# SparkFun_Noisy_Cricket.net
KiCad netlist of a schematic drawn in EAGLE
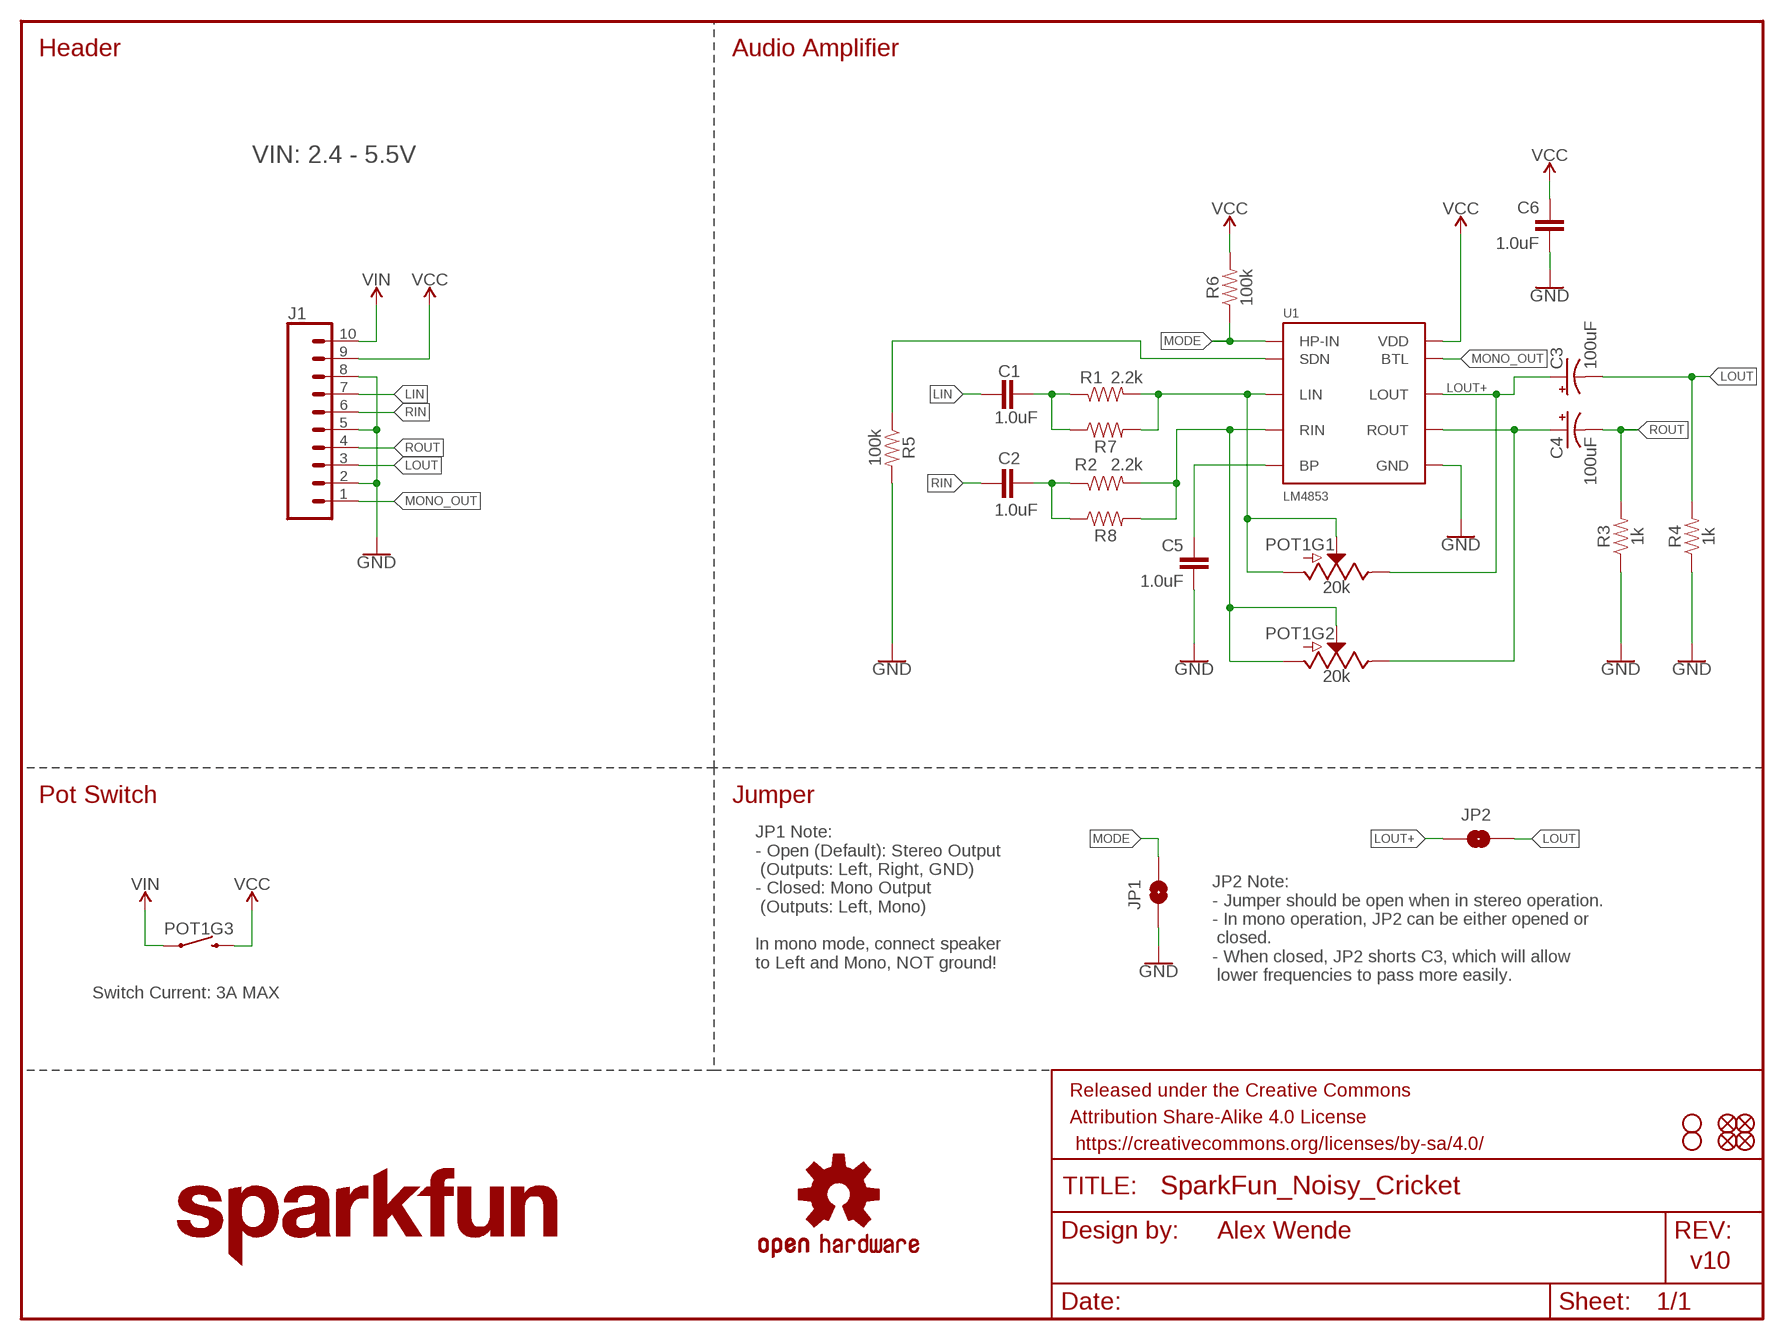
[diagram p0: schematic, sheet 1]

(export (version "E")
  (design (tool "Eeschema 10.0.6"))
  (components
    (comp (ref "C1")
      (value "1.0uF")
      (footprint "eagle-import:0603")
      (libsource (lib "eagle-import") (part "1.0UF-0603-16V-10%-X7R"))
    )
    (comp (ref "C2")
      (value "1.0uF")
      (footprint "eagle-import:0603")
      (libsource (lib "eagle-import") (part "1.0UF-0603-16V-10%-X7R"))
    )
    (comp (ref "C3")
      (value "100uF")
      (footprint "eagle-import:PANASONIC_D")
      (libsource (lib "eagle-import") (part "100UF-POLAR-25V-20%(ELEC)"))
    )
    (comp (ref "C4")
      (value "100uF")
      (footprint "eagle-import:PANASONIC_D")
      (libsource (lib "eagle-import") (part "100UF-POLAR-25V-20%(ELEC)"))
    )
    (comp (ref "C5")
      (value "1.0uF")
      (footprint "eagle-import:0603")
      (libsource (lib "eagle-import") (part "1.0UF-0603-16V-10%-X7R"))
    )
    (comp (ref "C6")
      (value "1.0uF")
      (footprint "eagle-import:0603")
      (libsource (lib "eagle-import") (part "1.0UF-0603-16V-10%-X7R"))
    )
    (comp (ref "FD1")
      (value "FIDUCIALUFIDUCIAL")
      (footprint "eagle-import:FIDUCIAL-MICRO")
      (libsource (lib "eagle-import") (part "FIDUCIALUFIDUCIAL"))
    )
    (comp (ref "FD2")
      (value "FIDUCIALUFIDUCIAL")
      (footprint "eagle-import:FIDUCIAL-MICRO")
      (libsource (lib "eagle-import") (part "FIDUCIALUFIDUCIAL"))
    )
    (comp (ref "FD3")
      (value "FIDUCIALUFIDUCIAL")
      (footprint "eagle-import:FIDUCIAL-MICRO")
      (libsource (lib "eagle-import") (part "FIDUCIALUFIDUCIAL"))
    )
    (comp (ref "FD4")
      (value "FIDUCIALUFIDUCIAL")
      (footprint "eagle-import:FIDUCIAL-MICRO")
      (libsource (lib "eagle-import") (part "FIDUCIALUFIDUCIAL"))
    )
    (comp (ref "FRAME1")
      (value "FRAME-LETTER")
      (footprint "eagle-import:CREATIVE_COMMONS")
      (libsource (lib "eagle-import") (part "FRAME-LETTER"))
    )
    (comp (ref "H1")
      (value "STAND-OFF")
      (footprint "eagle-import:STAND-OFF")
      (libsource (lib "eagle-import") (part "STAND-OFF"))
    )
    (comp (ref "H2")
      (value "STAND-OFF")
      (footprint "eagle-import:STAND-OFF")
      (libsource (lib "eagle-import") (part "STAND-OFF"))
    )
    (comp (ref "J1")
      (value "CONN_10NO_SILK_PTH_FEMALE")
      (footprint "eagle-import:1X10_NO_SILK")
      (libsource (lib "eagle-import") (part "CONN_10NO_SILK_PTH_FEMALE"))
    )
    (comp (ref "JP1")
      (value "JUMPER-SMT_2_NO_NO-SILK")
      (footprint "eagle-import:SMT-JUMPER_2_NO_NO-SILK")
      (libsource (lib "eagle-import") (part "JUMPER-SMT_2_NO_NO-SILK"))
    )
    (comp (ref "JP2")
      (value "JUMPER-SMT_2_NO_NO-SILK")
      (footprint "eagle-import:SMT-JUMPER_2_NO_NO-SILK")
      (libsource (lib "eagle-import") (part "JUMPER-SMT_2_NO_NO-SILK"))
    )
    (comp (ref "LOGO1")
      (value "SFE_LOGO_NAME.1_INCH")
      (footprint "eagle-import:SFE_LOGO_NAME_.1")
      (libsource (lib "eagle-import") (part "SFE_LOGO_NAME.1_INCH"))
    )
    (comp (ref "LOGO2")
      (value "OSHW-LOGOS")
      (footprint "eagle-import:OSHW-LOGO-S")
      (libsource (lib "eagle-import") (part "OSHW-LOGOS"))
    )
    (comp (ref "POT1")
      (value "20k")
      (footprint "eagle-import:POT-DUAL-SWITCH-PTH")
      (libsource (lib "eagle-import") (part "POTENTIOMETER_DUAL_W/SWITCH"))
    )
    (comp (ref "R1")
      (value "2.2k")
      (footprint "eagle-import:0603")
      (libsource (lib "eagle-import") (part "2.2KOHM-0603-1/10W-1%"))
    )
    (comp (ref "R2")
      (value "2.2k")
      (footprint "eagle-import:0603")
      (libsource (lib "eagle-import") (part "2.2KOHM-0603-1/10W-1%"))
    )
    (comp (ref "R3")
      (value "1k")
      (footprint "eagle-import:0603")
      (libsource (lib "eagle-import") (part "1KOHM-0603-1/10W-1%"))
    )
    (comp (ref "R4")
      (value "1k")
      (footprint "eagle-import:0603")
      (libsource (lib "eagle-import") (part "1KOHM-0603-1/10W-1%"))
    )
    (comp (ref "R5")
      (value "100k")
      (footprint "eagle-import:0603")
      (libsource (lib "eagle-import") (part "100KOHM-0603-1/10W-1%"))
    )
    (comp (ref "R6")
      (value "100k")
      (footprint "eagle-import:0603")
      (libsource (lib "eagle-import") (part "100KOHM-0603-1/10W-1%"))
    )
    (comp (ref "R7")
      (value "RESISTORAXIAL-0.3-KIT")
      (footprint "eagle-import:AXIAL-0.3-KIT")
      (libsource (lib "eagle-import") (part "RESISTORAXIAL-0.3-KIT"))
    )
    (comp (ref "R8")
      (value "RESISTORAXIAL-0.3-KIT")
      (footprint "eagle-import:AXIAL-0.3-KIT")
      (libsource (lib "eagle-import") (part "RESISTORAXIAL-0.3-KIT"))
    )
    (comp (ref "U1")
      (value "LM4853")
      (footprint "eagle-import:TFSOP-10")
      (libsource (lib "eagle-import") (part "LM4853"))
    )
  )
  (nets
    (net (code "1") (name "GND") (class "Default")
      (node (ref "C5") (pin "2") (pinfunction "2_2") (pintype "passive"))
      (node (ref "C6") (pin "2") (pinfunction "2_2") (pintype "passive"))
      (node (ref "J1") (pin "2") (pinfunction "2_2") (pintype "passive"))
      (node (ref "J1") (pin "5") (pinfunction "5_5") (pintype "passive"))
      (node (ref "J1") (pin "8") (pinfunction "8_8") (pintype "passive"))
      (node (ref "JP1") (pin "1") (pinfunction "1_1") (pintype "passive"))
      (node (ref "R3") (pin "1") (pinfunction "1_1") (pintype "passive"))
      (node (ref "R4") (pin "1") (pinfunction "1_1") (pintype "passive"))
      (node (ref "R5") (pin "2") (pinfunction "2_2") (pintype "passive"))
      (node (ref "U1") (pin "GND") (pinfunction "GND_GND") (pintype "bidirectional"))
    )
    (net (code "2") (name "LIN") (class "Default")
      (node (ref "C1") (pin "1") (pinfunction "1_1") (pintype "passive"))
      (node (ref "J1") (pin "7") (pinfunction "7_7") (pintype "passive"))
    )
    (net (code "3") (name "LOUT") (class "Default")
      (node (ref "C3") (pin "-") (pinfunction "-_-") (pintype "passive"))
      (node (ref "J1") (pin "3") (pinfunction "3_3") (pintype "passive"))
      (node (ref "JP2") (pin "2") (pinfunction "2_2") (pintype "passive"))
      (node (ref "R4") (pin "2") (pinfunction "2_2") (pintype "passive"))
    )
    (net (code "4") (name "LOUT+") (class "Default")
      (node (ref "C3") (pin "+") (pinfunction "+_+") (pintype "passive"))
      (node (ref "JP2") (pin "1") (pinfunction "1_1") (pintype "passive"))
      (node (ref "POT1") (pin "A3") (pinfunction "E_A3") (pintype "passive"))
      (node (ref "U1") (pin "LOUT") (pinfunction "LOUT_LOUT") (pintype "bidirectional"))
    )
    (net (code "5") (name "MODE") (class "Default")
      (node (ref "JP1") (pin "2") (pinfunction "2_2") (pintype "passive"))
      (node (ref "R6") (pin "1") (pinfunction "1_1") (pintype "passive"))
      (node (ref "U1") (pin "HP-IN") (pinfunction "HP-IN_HP-IN") (pintype "bidirectional"))
    )
    (net (code "6") (name "MONO_OUT") (class "Default")
      (node (ref "J1") (pin "1") (pinfunction "1_1") (pintype "passive"))
      (node (ref "U1") (pin "BTL") (pinfunction "BTL_BTL") (pintype "bidirectional"))
    )
    (net (code "7") (name "Net-(C5-Pad1)") (class "Default")
      (node (ref "C5") (pin "1") (pinfunction "1_1") (pintype "passive"))
      (node (ref "U1") (pin "BP") (pinfunction "BP_BP") (pintype "bidirectional"))
    )
    (net (code "8") (name "Net-(POT1A-A)") (class "Default")
      (node (ref "POT1") (pin "A1") (pinfunction "A_A1") (pintype "passive"))
      (node (ref "POT1") (pin "A2") (pinfunction "S_A2") (pintype "passive"))
      (node (ref "R1") (pin "2") (pinfunction "2_2") (pintype "passive"))
      (node (ref "R7") (pin "P$2") (pinfunction "2_P$2") (pintype "passive"))
      (node (ref "U1") (pin "LIN") (pinfunction "LIN_LIN") (pintype "bidirectional"))
    )
    (net (code "9") (name "Net-(POT1B-A)") (class "Default")
      (node (ref "POT1") (pin "B1") (pinfunction "A_B1") (pintype "passive"))
      (node (ref "POT1") (pin "B2") (pinfunction "S_B2") (pintype "passive"))
      (node (ref "R2") (pin "2") (pinfunction "2_2") (pintype "passive"))
      (node (ref "R8") (pin "P$2") (pinfunction "2_P$2") (pintype "passive"))
      (node (ref "U1") (pin "RIN") (pinfunction "RIN_RIN") (pintype "bidirectional"))
    )
    (net (code "10") (name "Net-(POT1B-E)") (class "Default")
      (node (ref "C4") (pin "+") (pinfunction "+_+") (pintype "passive"))
      (node (ref "POT1") (pin "B3") (pinfunction "E_B3") (pintype "passive"))
      (node (ref "U1") (pin "ROUT") (pinfunction "ROUT_ROUT") (pintype "bidirectional"))
    )
    (net (code "11") (name "Net-(R5-Pad1)") (class "Default")
      (node (ref "R5") (pin "1") (pinfunction "1_1") (pintype "passive"))
      (node (ref "U1") (pin "SDN") (pinfunction "SDN_SDN") (pintype "bidirectional"))
    )
    (net (code "12") (name "Net-(R7-1)") (class "Default")
      (node (ref "C1") (pin "2") (pinfunction "2_2") (pintype "passive"))
      (node (ref "R1") (pin "1") (pinfunction "1_1") (pintype "passive"))
      (node (ref "R7") (pin "P$1") (pinfunction "1_P$1") (pintype "passive"))
    )
    (net (code "13") (name "Net-(R8-1)") (class "Default")
      (node (ref "C2") (pin "2") (pinfunction "2_2") (pintype "passive"))
      (node (ref "R2") (pin "1") (pinfunction "1_1") (pintype "passive"))
      (node (ref "R8") (pin "P$1") (pinfunction "1_P$1") (pintype "passive"))
    )
    (net (code "14") (name "RIN") (class "Default")
      (node (ref "C2") (pin "1") (pinfunction "1_1") (pintype "passive"))
      (node (ref "J1") (pin "6") (pinfunction "6_6") (pintype "passive"))
    )
    (net (code "15") (name "ROUT") (class "Default")
      (node (ref "C4") (pin "-") (pinfunction "-_-") (pintype "passive"))
      (node (ref "J1") (pin "4") (pinfunction "4_4") (pintype "passive"))
      (node (ref "R3") (pin "2") (pinfunction "2_2") (pintype "passive"))
    )
    (net (code "16") (name "VCC") (class "Default")
      (node (ref "C6") (pin "1") (pinfunction "1_1") (pintype "passive"))
      (node (ref "J1") (pin "9") (pinfunction "9_9") (pintype "passive"))
      (node (ref "POT1") (pin "SW2") (pinfunction "2_SW2") (pintype "passive"))
      (node (ref "R6") (pin "2") (pinfunction "2_2") (pintype "passive"))
      (node (ref "U1") (pin "VDD") (pinfunction "VDD_VDD") (pintype "bidirectional"))
    )
    (net (code "17") (name "VIN") (class "Default")
      (node (ref "J1") (pin "10") (pinfunction "10_10") (pintype "passive"))
      (node (ref "POT1") (pin "SW1") (pinfunction "1_SW1") (pintype "passive"))
    )
  )
)
